# MotorsBoost.net
KiCad netlist of a schematic drawn in Altium Designer
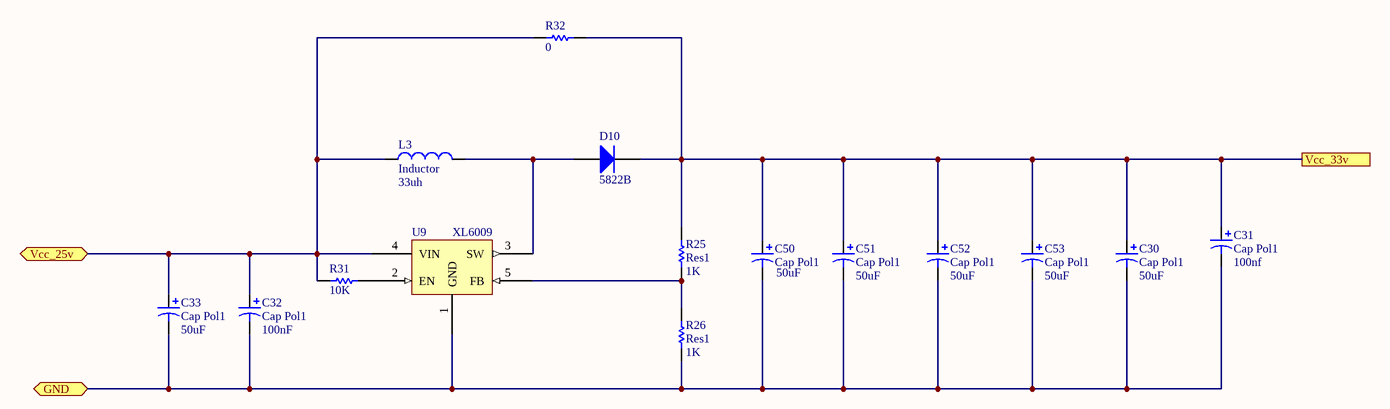
[diagram p0: MotorsBoost.SchDoc]

(export (version "E")
  (design (tool "Eeschema 10.0.6"))
  (components
    (comp (ref "C30")
      (value "Cap Pol1")
      (footprint "Tantalum_9545")
      (description "Polarized Capacitor (Radial)")
      (fields (field (name "ALTIUM_VALUE") "50uF") (field (name "PUBLISHER") "Altium Limited"))
      (libsource (lib "Miscellaneous Devices") (part "Cap Pol1"))
    )
    (comp (ref "C31")
      (value "Cap Pol1")
      (footprint "1206_SMD")
      (description "Polarized Capacitor (Radial)")
      (fields (field (name "ALTIUM_VALUE") "100nf") (field (name "PUBLISHER") "Altium Limited"))
      (libsource (lib "Miscellaneous Devices") (part "Cap Pol1"))
    )
    (comp (ref "C32")
      (value "Cap Pol1")
      (footprint "1206_SMD")
      (description "Polarized Capacitor (Radial)")
      (fields (field (name "ALTIUM_VALUE") "100nF") (field (name "PUBLISHER") "Altium Limited"))
      (libsource (lib "Miscellaneous Devices") (part "Cap Pol1"))
    )
    (comp (ref "C33")
      (value "Cap Pol1")
      (footprint "Tantalum_9545")
      (description "Polarized Capacitor (Radial)")
      (fields (field (name "ALTIUM_VALUE") "50uF") (field (name "PUBLISHER") "Altium Limited"))
      (libsource (lib "Miscellaneous Devices") (part "Cap Pol1"))
    )
    (comp (ref "C50")
      (value "Cap Pol1")
      (footprint "Tantalum_9545")
      (description "Polarized Capacitor (Radial)")
      (fields (field (name "ALTIUM_VALUE") "50uF") (field (name "PUBLISHER") "Altium Limited"))
      (libsource (lib "Miscellaneous Devices") (part "Cap Pol1"))
    )
    (comp (ref "C51")
      (value "Cap Pol1")
      (footprint "Tantalum_9545")
      (description "Polarized Capacitor (Radial)")
      (fields (field (name "ALTIUM_VALUE") "50uF") (field (name "PUBLISHER") "Altium Limited"))
      (libsource (lib "Miscellaneous Devices") (part "Cap Pol1"))
    )
    (comp (ref "C52")
      (value "Cap Pol1")
      (footprint "Tantalum_9545")
      (description "Polarized Capacitor (Radial)")
      (fields (field (name "ALTIUM_VALUE") "50uF") (field (name "PUBLISHER") "Altium Limited"))
      (libsource (lib "Miscellaneous Devices") (part "Cap Pol1"))
    )
    (comp (ref "C53")
      (value "Cap Pol1")
      (footprint "Tantalum_9545")
      (description "Polarized Capacitor (Radial)")
      (fields (field (name "ALTIUM_VALUE") "50uF") (field (name "PUBLISHER") "Altium Limited"))
      (libsource (lib "Miscellaneous Devices") (part "Cap Pol1"))
    )
    (comp (ref "D10")
      (value "5822B")
      (footprint "SMB")
      (description "Default Diode")
      (fields (field (name "PUBLISHER") "Altium Limited"))
      (libsource (lib "Miscellaneous Devices") (part "Diode"))
    )
    (comp (ref "L3")
      (value "Inductor")
      (footprint "inductor_12.3*12.3")
      (fields (field (name "ALTIUM_VALUE") "33uh") (field (name "PUBLISHER") "Altium Limited"))
      (libsource (lib "Miscellaneous Devices") (part "Inductor"))
    )
    (comp (ref "R25")
      (value "Res1")
      (footprint "0805_smd")
      (description "Resistor")
      (fields (field (name "ALTIUM_VALUE") "1K") (field (name "PUBLISHER") "Altium Limited"))
      (libsource (lib "Miscellaneous Devices") (part "Res1"))
    )
    (comp (ref "R26")
      (value "Res1")
      (footprint "0805_smd")
      (description "Resistor")
      (fields (field (name "ALTIUM_VALUE") "1K") (field (name "PUBLISHER") "Altium Limited"))
      (libsource (lib "Miscellaneous Devices") (part "Res1"))
    )
    (comp (ref "R31")
      (value "10K")
      (footprint "0805_smd")
      (description "Resistor")
      (fields (field (name "PUBLISHER") "Altium Limited"))
      (libsource (lib "Miscellaneous Devices") (part "Res1"))
    )
    (comp (ref "R32")
      (value "0")
      (footprint "2010_smd")
      (description "Resistor")
      (fields (field (name "PUBLISHER") "Altium Limited"))
      (libsource (lib "Miscellaneous Devices") (part "Res1"))
    )
    (comp (ref "U9")
      (value "XL6009")
      (footprint "TO263-5L")
      (description "Voltage Booster")
      (libsource (lib "CustomLib_Ver01") (part "XL6009"))
    )
  )
  (nets
    (net (code "1") (name "/GND") (class "Default")
      (node (ref "C30") (pin "2") (pinfunction "2_2") (pintype "passive"))
      (node (ref "C31") (pin "2") (pinfunction "2_2") (pintype "passive"))
      (node (ref "C32") (pin "2") (pinfunction "2_2") (pintype "passive"))
      (node (ref "C33") (pin "2") (pinfunction "2_2") (pintype "passive"))
      (node (ref "C50") (pin "2") (pinfunction "2_2") (pintype "passive"))
      (node (ref "C51") (pin "2") (pinfunction "2_2") (pintype "passive"))
      (node (ref "C52") (pin "2") (pinfunction "2_2") (pintype "passive"))
      (node (ref "C53") (pin "2") (pinfunction "2_2") (pintype "passive"))
      (node (ref "R26") (pin "1") (pinfunction "1_1") (pintype "passive"))
      (node (ref "U9") (pin "1") (pinfunction "GND_1") (pintype "power_in"))
    )
    (net (code "2") (name "/Vcc_25v") (class "Default")
      (node (ref "C32") (pin "1") (pinfunction "1_1") (pintype "passive"))
      (node (ref "C33") (pin "1") (pinfunction "1_1") (pintype "passive"))
      (node (ref "L3") (pin "1") (pinfunction "1_1") (pintype "passive"))
      (node (ref "R31") (pin "1") (pinfunction "1_1") (pintype "passive"))
      (node (ref "R32") (pin "1") (pinfunction "1_1") (pintype "passive"))
      (node (ref "U9") (pin "4") (pinfunction "VIN_4") (pintype "power_in"))
    )
    (net (code "3") (name "/Vcc_33v") (class "Default")
      (node (ref "C30") (pin "1") (pinfunction "1_1") (pintype "passive"))
      (node (ref "C31") (pin "1") (pinfunction "1_1") (pintype "passive"))
      (node (ref "C50") (pin "1") (pinfunction "1_1") (pintype "passive"))
      (node (ref "C51") (pin "1") (pinfunction "1_1") (pintype "passive"))
      (node (ref "C52") (pin "1") (pinfunction "1_1") (pintype "passive"))
      (node (ref "C53") (pin "1") (pinfunction "1_1") (pintype "passive"))
      (node (ref "D10") (pin "2") (pinfunction "K_2") (pintype "passive"))
      (node (ref "R25") (pin "2") (pinfunction "2_2") (pintype "passive"))
      (node (ref "R32") (pin "2") (pinfunction "2_2") (pintype "passive"))
    )
    (net (code "4") (name "Net-(D10-A)") (class "Default")
      (node (ref "D10") (pin "1") (pinfunction "A_1") (pintype "passive"))
      (node (ref "L3") (pin "2") (pinfunction "2_2") (pintype "passive"))
      (node (ref "U9") (pin "3") (pinfunction "SW_3") (pintype "output"))
    )
    (net (code "5") (name "Net-(U9-EN)") (class "Default")
      (node (ref "R31") (pin "2") (pinfunction "2_2") (pintype "passive"))
      (node (ref "U9") (pin "2") (pinfunction "EN_2") (pintype "input"))
    )
    (net (code "6") (name "Net-(U9-FB)") (class "Default")
      (node (ref "R25") (pin "1") (pinfunction "1_1") (pintype "passive"))
      (node (ref "R26") (pin "2") (pinfunction "2_2") (pintype "passive"))
      (node (ref "U9") (pin "5") (pinfunction "FB_5") (pintype "input"))
    )
  )
)
